# Tonuino_V1_0.net
KiCad netlist of a schematic drawn in EAGLE
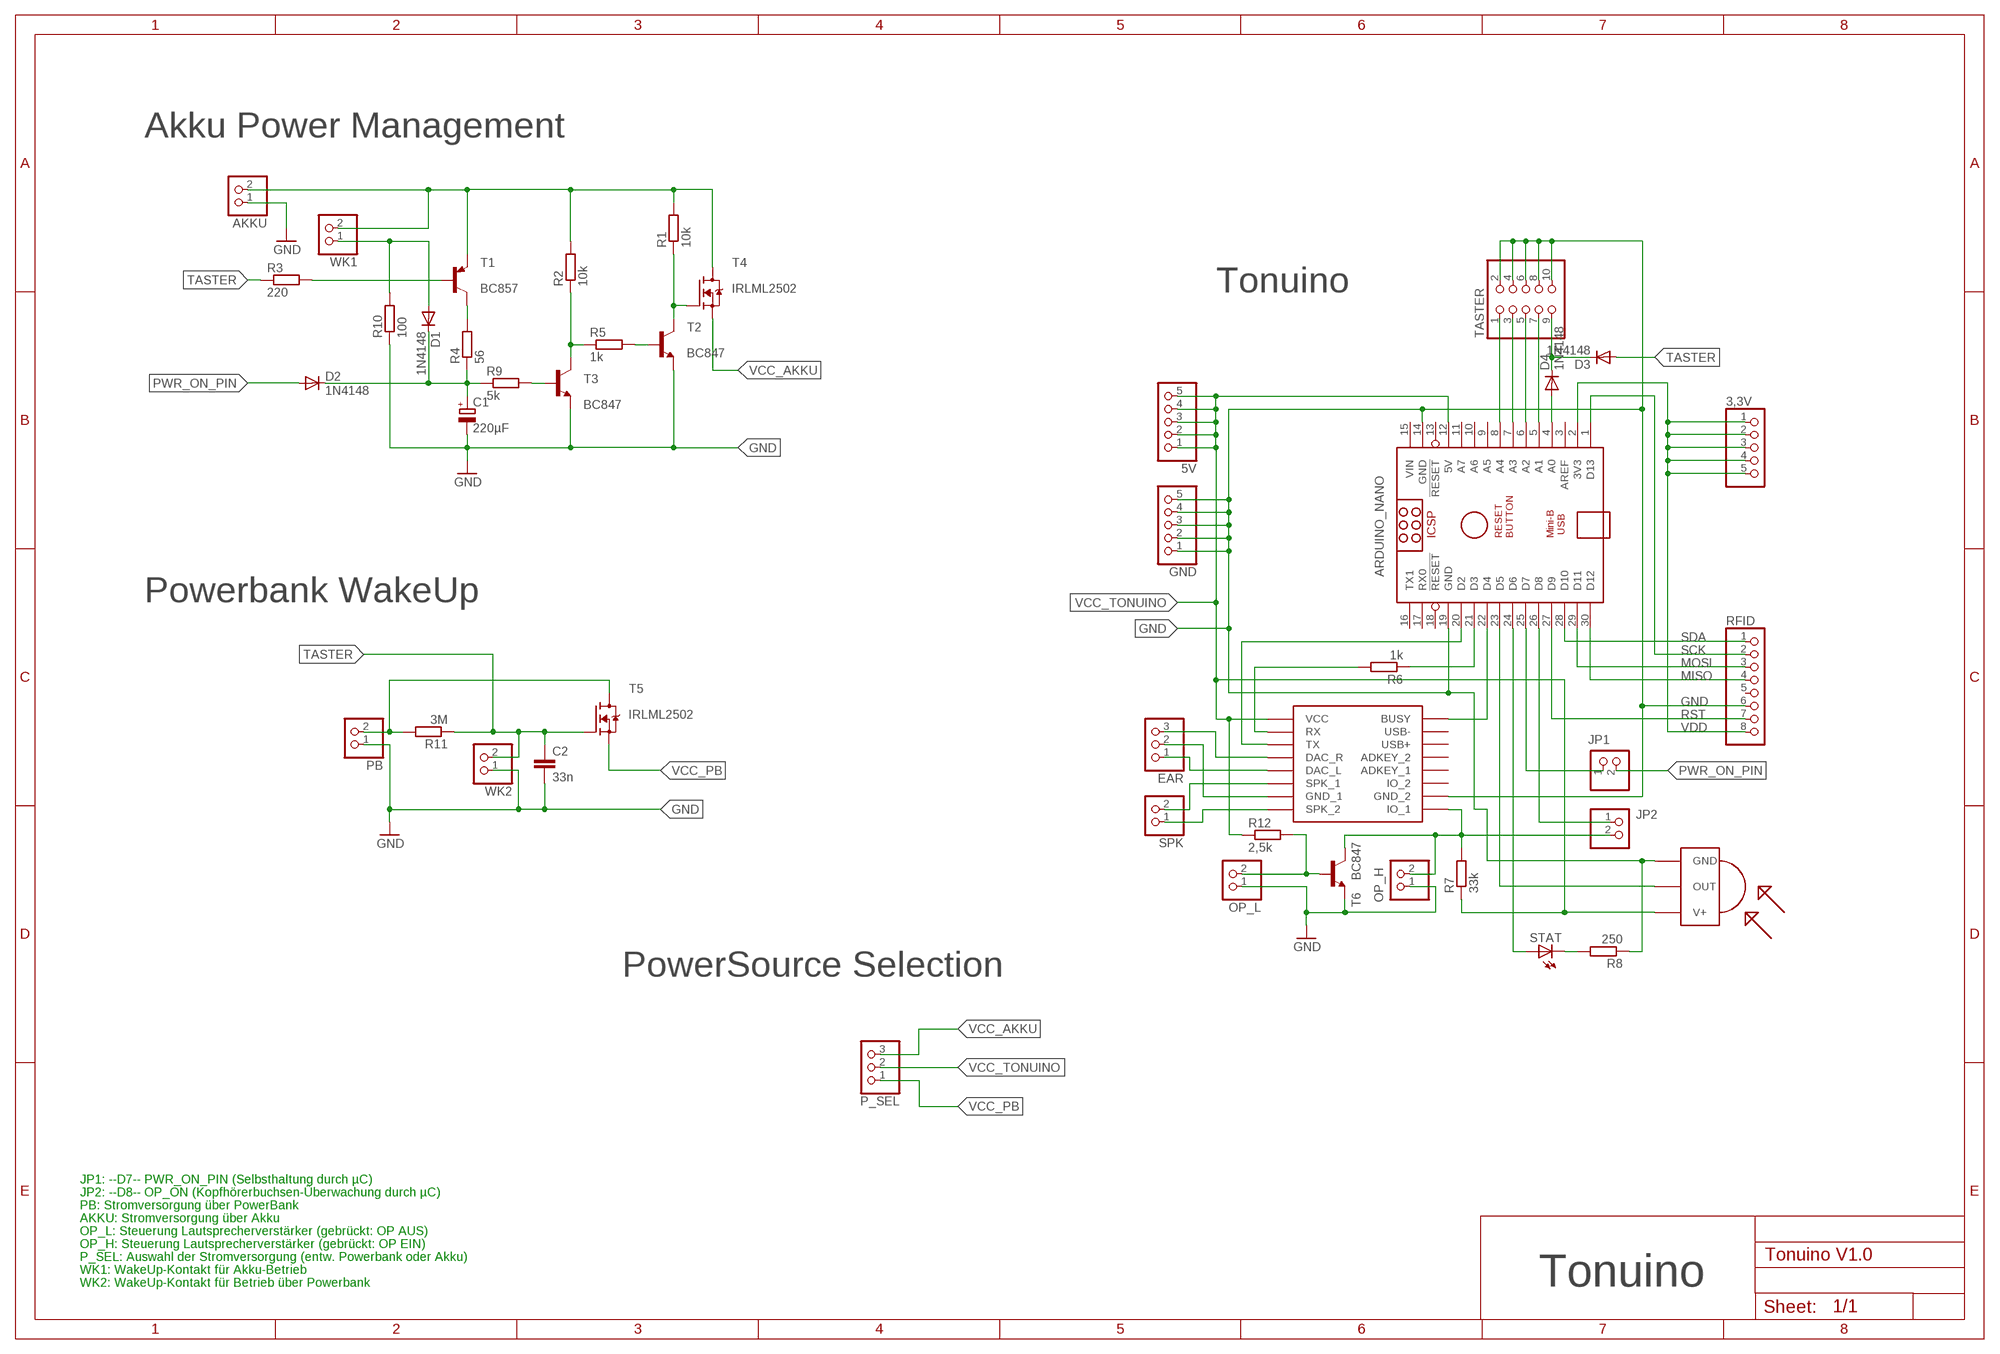
[diagram p0: schematic, sheet 1]

(export (version "E")
  (design (tool "Eeschema 10.0.6"))
  (components
    (comp (ref "3,3V")
      (value "PINHD-1X5")
      (footprint "eagle-import:1X05")
      (libsource (lib "eagle-import") (part "PINHD-1X5"))
    )
    (comp (ref "5V")
      (value "PINHD-1X5")
      (footprint "eagle-import:1X05")
      (libsource (lib "eagle-import") (part "PINHD-1X5"))
    )
    (comp (ref "AKKU")
      (value "PINHD-1X2")
      (footprint "eagle-import:1X02")
      (libsource (lib "eagle-import") (part "PINHD-1X2"))
    )
    (comp (ref "ARDUINO_NANO")
      (value "ARDUINO_NANO")
      (footprint "eagle-import:ARDUINO_NANO")
      (libsource (lib "eagle-import") (part "ARDUINO_NANO"))
    )
    (comp (ref "C1")
      (value "220µF")
      (footprint "eagle-import:E5-13")
      (libsource (lib "eagle-import") (part "CPOL-EUE5-13"))
    )
    (comp (ref "C2")
      (value "33n")
      (footprint "eagle-import:C0805")
      (libsource (lib "eagle-import") (part "C-EUC0805"))
    )
    (comp (ref "D1")
      (value "1N4148")
      (footprint "eagle-import:SOD323-W")
      (libsource (lib "eagle-import") (part "DIODE-SOD323-W"))
    )
    (comp (ref "D2")
      (value "1N4148")
      (footprint "eagle-import:SOD323-W")
      (libsource (lib "eagle-import") (part "DIODE-SOD323-W"))
    )
    (comp (ref "D3")
      (value "1N4148")
      (footprint "eagle-import:SOD323-W")
      (libsource (lib "eagle-import") (part "DIODE-SOD323-W"))
    )
    (comp (ref "D4")
      (value "1N4148")
      (footprint "eagle-import:SOD323-W")
      (libsource (lib "eagle-import") (part "DIODE-SOD323-W"))
    )
    (comp (ref "EAR")
      (value "PINHD-1X3")
      (footprint "eagle-import:1X03")
      (libsource (lib "eagle-import") (part "PINHD-1X3"))
    )
    (comp (ref "GND")
      (value "PINHD-1X5")
      (footprint "eagle-import:1X05")
      (libsource (lib "eagle-import") (part "PINHD-1X5"))
    )
    (comp (ref "JP1")
      (value "PINHD-1X2")
      (footprint "eagle-import:1X02")
      (libsource (lib "eagle-import") (part "PINHD-1X2"))
    )
    (comp (ref "JP2")
      (value "PINHD-1X2")
      (footprint "eagle-import:1X02")
      (libsource (lib "eagle-import") (part "PINHD-1X2"))
    )
    (comp (ref "OP_H")
      (value "PINHD-1X2")
      (footprint "eagle-import:1X02")
      (libsource (lib "eagle-import") (part "PINHD-1X2"))
    )
    (comp (ref "OP_L")
      (value "PINHD-1X2")
      (footprint "eagle-import:1X02")
      (libsource (lib "eagle-import") (part "PINHD-1X2"))
    )
    (comp (ref "PB")
      (value "PINHD-1X2")
      (footprint "eagle-import:1X02")
      (libsource (lib "eagle-import") (part "PINHD-1X2"))
    )
    (comp (ref "P_SEL")
      (value "PINHD-1X3")
      (footprint "eagle-import:1X03")
      (libsource (lib "eagle-import") (part "PINHD-1X3"))
    )
    (comp (ref "R1")
      (value "10k")
      (footprint "eagle-import:R1206")
      (libsource (lib "eagle-import") (part "R-EU_R1206"))
    )
    (comp (ref "R2")
      (value "10k")
      (footprint "eagle-import:R1206")
      (libsource (lib "eagle-import") (part "R-EU_R1206"))
    )
    (comp (ref "R3")
      (value "220")
      (footprint "eagle-import:R1206")
      (libsource (lib "eagle-import") (part "R-EU_R1206"))
    )
    (comp (ref "R4")
      (value "56")
      (footprint "eagle-import:R1206")
      (libsource (lib "eagle-import") (part "R-EU_R1206"))
    )
    (comp (ref "R5")
      (value "1k")
      (footprint "eagle-import:R1206")
      (libsource (lib "eagle-import") (part "R-EU_R1206"))
    )
    (comp (ref "R6")
      (value "1k")
      (footprint "eagle-import:R1206")
      (libsource (lib "eagle-import") (part "R-EU_R1206"))
    )
    (comp (ref "R7")
      (value "33k")
      (footprint "eagle-import:R1206")
      (libsource (lib "eagle-import") (part "R-EU_R1206"))
    )
    (comp (ref "R8")
      (value "250")
      (footprint "eagle-import:R1206")
      (libsource (lib "eagle-import") (part "R-EU_R1206"))
    )
    (comp (ref "R9")
      (value "5k")
      (footprint "eagle-import:R1206")
      (libsource (lib "eagle-import") (part "R-EU_R1206"))
    )
    (comp (ref "R10")
      (value "100")
      (footprint "eagle-import:R1206")
      (libsource (lib "eagle-import") (part "R-EU_R1206"))
    )
    (comp (ref "R11")
      (value "3M")
      (footprint "eagle-import:R1206")
      (libsource (lib "eagle-import") (part "R-EU_R1206"))
    )
    (comp (ref "R12")
      (value "2,5k")
      (footprint "eagle-import:R1206")
      (libsource (lib "eagle-import") (part "R-EU_R1206"))
    )
    (comp (ref "RFID")
      (value "PINHD-1X8")
      (footprint "eagle-import:1X08")
      (libsource (lib "eagle-import") (part "PINHD-1X8"))
    )
    (comp (ref "SPK")
      (value "PINHD-1X2")
      (footprint "eagle-import:1X02")
      (libsource (lib "eagle-import") (part "PINHD-1X2"))
    )
    (comp (ref "STAT")
      (value "LED5MM")
      (footprint "eagle-import:LED5MM")
      (libsource (lib "eagle-import") (part "LED5MM"))
    )
    (comp (ref "T1")
      (value "BC857")
      (footprint "eagle-import:SOT23-BEC")
      (libsource (lib "eagle-import") (part "-PNP-SOT23-BECBC857A"))
    )
    (comp (ref "T2")
      (value "BC847")
      (footprint "eagle-import:SOT23")
      (libsource (lib "eagle-import") (part "BC847"))
    )
    (comp (ref "T3")
      (value "BC847")
      (footprint "eagle-import:SOT23")
      (libsource (lib "eagle-import") (part "BC847"))
    )
    (comp (ref "T4")
      (value "IRLML2502")
      (footprint "eagle-import:SOT23")
      (libsource (lib "eagle-import") (part "IRLML2502"))
    )
    (comp (ref "T5")
      (value "IRLML2502")
      (footprint "eagle-import:SOT23")
      (libsource (lib "eagle-import") (part "IRLML2502"))
    )
    (comp (ref "T6")
      (value "BC847")
      (footprint "eagle-import:SOT23")
      (libsource (lib "eagle-import") (part "BC847"))
    )
    (comp (ref "TASTER")
      (value "PINHD-2X5")
      (footprint "eagle-import:2X05")
      (libsource (lib "eagle-import") (part "PINHD-2X5"))
    )
    (comp (ref "TSOP1")
      (value "TSOP1730")
      (footprint "eagle-import:TSOP17XX")
      (libsource (lib "eagle-import") (part "TSOP1730"))
    )
    (comp (ref "U$2")
      (value "DFPLAYER")
      (footprint "eagle-import:DFPLAYER")
      (libsource (lib "eagle-import") (part "DFPLAYER"))
    )
    (comp (ref "WK1")
      (value "PINHD-1X2")
      (footprint "eagle-import:1X02")
      (libsource (lib "eagle-import") (part "PINHD-1X2"))
    )
    (comp (ref "WK2")
      (value "PINHD-1X2")
      (footprint "eagle-import:1X02")
      (libsource (lib "eagle-import") (part "PINHD-1X2"))
    )
  )
  (nets
    (net (code "1") (name "/MISO") (class "Default")
      (node (ref "ARDUINO_NANO") (pin "30") (pinfunction "D12_30") (pintype "bidirectional"))
      (node (ref "RFID") (pin "4") (pinfunction "4_4") (pintype "passive"))
    )
    (net (code "2") (name "/MOSI") (class "Default")
      (node (ref "ARDUINO_NANO") (pin "29") (pinfunction "D11_29") (pintype "bidirectional"))
      (node (ref "RFID") (pin "3") (pinfunction "3_3") (pintype "passive"))
    )
    (net (code "3") (name "/RST") (class "Default")
      (node (ref "ARDUINO_NANO") (pin "27") (pinfunction "D9_27") (pintype "bidirectional"))
      (node (ref "RFID") (pin "7") (pinfunction "7_7") (pintype "passive"))
    )
    (net (code "4") (name "/SCK") (class "Default")
      (node (ref "ARDUINO_NANO") (pin "1") (pinfunction "D13_1") (pintype "bidirectional"))
      (node (ref "RFID") (pin "2") (pinfunction "2_2") (pintype "passive"))
    )
    (net (code "5") (name "/SDA") (class "Default")
      (node (ref "ARDUINO_NANO") (pin "28") (pinfunction "D10_28") (pintype "bidirectional"))
      (node (ref "RFID") (pin "1") (pinfunction "1_1") (pintype "passive"))
    )
    (net (code "6") (name "/VDD") (class "Default")
      (node (ref "3,3V") (pin "1") (pinfunction "1_1") (pintype "passive"))
      (node (ref "3,3V") (pin "2") (pinfunction "2_2") (pintype "passive"))
      (node (ref "3,3V") (pin "3") (pinfunction "3_3") (pintype "passive"))
      (node (ref "3,3V") (pin "4") (pinfunction "4_4") (pintype "passive"))
      (node (ref "3,3V") (pin "5") (pinfunction "5_5") (pintype "passive"))
      (node (ref "ARDUINO_NANO") (pin "2") (pinfunction "3V3_2") (pintype "output"))
      (node (ref "RFID") (pin "8") (pinfunction "8_8") (pintype "passive"))
    )
    (net (code "7") (name "/VIN") (class "Default")
      (node (ref "ARDUINO_NANO") (pin "15") (pinfunction "VIN_15") (pintype "power_in"))
    )
    (net (code "8") (name "GND") (class "Default")
      (node (ref "AKKU") (pin "1") (pinfunction "1_1") (pintype "passive"))
      (node (ref "ARDUINO_NANO") (pin "14") (pinfunction "GND_14") (pintype "power_in"))
      (node (ref "ARDUINO_NANO") (pin "19") (pinfunction "GND_19") (pintype "power_in"))
      (node (ref "C1") (pin "-") (pinfunction "-_-") (pintype "passive"))
      (node (ref "C2") (pin "2") (pinfunction "2_2") (pintype "passive"))
      (node (ref "GND") (pin "1") (pinfunction "1_1") (pintype "passive"))
      (node (ref "GND") (pin "2") (pinfunction "2_2") (pintype "passive"))
      (node (ref "GND") (pin "3") (pinfunction "3_3") (pintype "passive"))
      (node (ref "GND") (pin "4") (pinfunction "4_4") (pintype "passive"))
      (node (ref "GND") (pin "5") (pinfunction "5_5") (pintype "passive"))
      (node (ref "OP_H") (pin "1") (pinfunction "1_1") (pintype "passive"))
      (node (ref "OP_L") (pin "1") (pinfunction "1_1") (pintype "passive"))
      (node (ref "PB") (pin "1") (pinfunction "1_1") (pintype "passive"))
      (node (ref "R10") (pin "1") (pinfunction "1_1") (pintype "passive"))
      (node (ref "R8") (pin "1") (pinfunction "1_1") (pintype "passive"))
      (node (ref "RFID") (pin "6") (pinfunction "6_6") (pintype "passive"))
      (node (ref "T2") (pin "2") (pinfunction "E_2") (pintype "passive"))
      (node (ref "T3") (pin "2") (pinfunction "E_2") (pintype "passive"))
      (node (ref "T6") (pin "2") (pinfunction "E_2") (pintype "passive"))
      (node (ref "TASTER") (pin "10") (pinfunction "10_10") (pintype "passive"))
      (node (ref "TASTER") (pin "2") (pinfunction "2_2") (pintype "passive"))
      (node (ref "TASTER") (pin "4") (pinfunction "4_4") (pintype "passive"))
      (node (ref "TASTER") (pin "6") (pinfunction "6_6") (pintype "passive"))
      (node (ref "TASTER") (pin "8") (pinfunction "8_8") (pintype "passive"))
      (node (ref "TSOP1") (pin "GND") (pinfunction "GND_GND") (pintype "bidirectional"))
      (node (ref "U$2") (pin "GND_2") (pinfunction "GND_2_GND_2") (pintype "bidirectional"))
      (node (ref "WK2") (pin "1") (pinfunction "1_1") (pintype "passive"))
    )
    (net (code "9") (name "Net-(ARDUINO_NANO-A0)") (class "Default")
      (node (ref "ARDUINO_NANO") (pin "4") (pinfunction "A0_4") (pintype "bidirectional"))
      (node (ref "D4") (pin "A") (pinfunction "A_A") (pintype "passive"))
    )
    (net (code "10") (name "Net-(ARDUINO_NANO-A1)") (class "Default")
      (node (ref "ARDUINO_NANO") (pin "5") (pinfunction "A1_5") (pintype "bidirectional"))
      (node (ref "TASTER") (pin "7") (pinfunction "7_7") (pintype "passive"))
    )
    (net (code "11") (name "Net-(ARDUINO_NANO-A2)") (class "Default")
      (node (ref "ARDUINO_NANO") (pin "6") (pinfunction "A2_6") (pintype "bidirectional"))
      (node (ref "TASTER") (pin "5") (pinfunction "5_5") (pintype "passive"))
    )
    (net (code "12") (name "Net-(ARDUINO_NANO-A3)") (class "Default")
      (node (ref "ARDUINO_NANO") (pin "7") (pinfunction "A3_7") (pintype "bidirectional"))
      (node (ref "TASTER") (pin "3") (pinfunction "3_3") (pintype "passive"))
    )
    (net (code "13") (name "Net-(ARDUINO_NANO-A4)") (class "Default")
      (node (ref "ARDUINO_NANO") (pin "8") (pinfunction "A4_8") (pintype "bidirectional"))
      (node (ref "TASTER") (pin "1") (pinfunction "1_1") (pintype "passive"))
    )
    (net (code "14") (name "Net-(ARDUINO_NANO-D2)") (class "Default")
      (node (ref "ARDUINO_NANO") (pin "20") (pinfunction "D2_20") (pintype "bidirectional"))
      (node (ref "U$2") (pin "TX") (pinfunction "TX_TX") (pintype "bidirectional"))
    )
    (net (code "15") (name "Net-(ARDUINO_NANO-D3)") (class "Default")
      (node (ref "ARDUINO_NANO") (pin "21") (pinfunction "D3_21") (pintype "bidirectional"))
      (node (ref "R6") (pin "1") (pinfunction "1_1") (pintype "passive"))
    )
    (net (code "16") (name "Net-(ARDUINO_NANO-D4)") (class "Default")
      (node (ref "ARDUINO_NANO") (pin "22") (pinfunction "D4_22") (pintype "bidirectional"))
      (node (ref "U$2") (pin "BUSY") (pinfunction "BUSY_BUSY") (pintype "bidirectional"))
    )
    (net (code "17") (name "Net-(ARDUINO_NANO-D5)") (class "Default")
      (node (ref "ARDUINO_NANO") (pin "23") (pinfunction "D5_23") (pintype "bidirectional"))
      (node (ref "TSOP1") (pin "OUT") (pinfunction "OUT_OUT") (pintype "bidirectional"))
    )
    (net (code "18") (name "Net-(ARDUINO_NANO-D6)") (class "Default")
      (node (ref "ARDUINO_NANO") (pin "24") (pinfunction "D6_24") (pintype "bidirectional"))
      (node (ref "STAT") (pin "A") (pinfunction "A_A") (pintype "passive"))
    )
    (net (code "19") (name "Net-(ARDUINO_NANO-D7)") (class "Default")
      (node (ref "ARDUINO_NANO") (pin "25") (pinfunction "D7_25") (pintype "bidirectional"))
      (node (ref "JP1") (pin "1") (pinfunction "1_1") (pintype "passive"))
    )
    (net (code "20") (name "Net-(ARDUINO_NANO-D8)") (class "Default")
      (node (ref "ARDUINO_NANO") (pin "26") (pinfunction "D8_26") (pintype "bidirectional"))
      (node (ref "JP2") (pin "1") (pinfunction "1_1") (pintype "passive"))
    )
    (net (code "21") (name "Net-(C1-Pad+)") (class "Default")
      (node (ref "C1") (pin "+") (pinfunction "+_+") (pintype "passive"))
      (node (ref "D1") (pin "C") (pinfunction "C_C") (pintype "passive"))
      (node (ref "D2") (pin "C") (pinfunction "C_C") (pintype "passive"))
      (node (ref "R4") (pin "1") (pinfunction "1_1") (pintype "passive"))
      (node (ref "R9") (pin "1") (pinfunction "1_1") (pintype "passive"))
    )
    (net (code "22") (name "Net-(D1-PadA)") (class "Default")
      (node (ref "D1") (pin "A") (pinfunction "A_A") (pintype "passive"))
      (node (ref "R10") (pin "2") (pinfunction "2_2") (pintype "passive"))
      (node (ref "WK1") (pin "1") (pinfunction "1_1") (pintype "passive"))
    )
    (net (code "23") (name "Net-(D3-PadC)") (class "Default")
      (node (ref "D3") (pin "C") (pinfunction "C_C") (pintype "passive"))
      (node (ref "D4") (pin "C") (pinfunction "C_C") (pintype "passive"))
      (node (ref "TASTER") (pin "9") (pinfunction "9_9") (pintype "passive"))
    )
    (net (code "24") (name "Net-(EAR-Pad1)") (class "Default")
      (node (ref "EAR") (pin "1") (pinfunction "1_1") (pintype "passive"))
      (node (ref "U$2") (pin "DAC_L") (pinfunction "DAC_L_DAC_L") (pintype "bidirectional"))
    )
    (net (code "25") (name "Net-(EAR-Pad2)") (class "Default")
      (node (ref "EAR") (pin "2") (pinfunction "2_2") (pintype "passive"))
      (node (ref "U$2") (pin "GND_1") (pinfunction "GND_1_GND_1") (pintype "bidirectional"))
    )
    (net (code "26") (name "Net-(EAR-Pad3)") (class "Default")
      (node (ref "EAR") (pin "3") (pinfunction "3_3") (pintype "passive"))
      (node (ref "U$2") (pin "DAC_R") (pinfunction "DAC_R_DAC_R") (pintype "bidirectional"))
    )
    (net (code "27") (name "Net-(R3-Pad2)") (class "Default")
      (node (ref "R3") (pin "2") (pinfunction "2_2") (pintype "passive"))
      (node (ref "T1") (pin "B") (pinfunction "B_B") (pintype "passive"))
    )
    (net (code "28") (name "Net-(R4-Pad2)") (class "Default")
      (node (ref "R4") (pin "2") (pinfunction "2_2") (pintype "passive"))
      (node (ref "T1") (pin "C") (pinfunction "C_C") (pintype "passive"))
    )
    (net (code "29") (name "Net-(R6-Pad2)") (class "Default")
      (node (ref "R6") (pin "2") (pinfunction "2_2") (pintype "passive"))
      (node (ref "U$2") (pin "RX") (pinfunction "RX_RX") (pintype "bidirectional"))
    )
    (net (code "30") (name "Net-(STAT-C)") (class "Default")
      (node (ref "R8") (pin "2") (pinfunction "2_2") (pintype "passive"))
      (node (ref "STAT") (pin "K") (pinfunction "C_K") (pintype "passive"))
    )
    (net (code "31") (name "Net-(T2-B)") (class "Default")
      (node (ref "R5") (pin "2") (pinfunction "2_2") (pintype "passive"))
      (node (ref "T2") (pin "1") (pinfunction "B_1") (pintype "passive"))
    )
    (net (code "32") (name "Net-(T2-C)") (class "Default")
      (node (ref "R1") (pin "1") (pinfunction "1_1") (pintype "passive"))
      (node (ref "T2") (pin "3") (pinfunction "C_3") (pintype "passive"))
      (node (ref "T4") (pin "1") (pinfunction "G_1") (pintype "passive"))
    )
    (net (code "33") (name "Net-(T3-B)") (class "Default")
      (node (ref "R9") (pin "2") (pinfunction "2_2") (pintype "passive"))
      (node (ref "T3") (pin "1") (pinfunction "B_1") (pintype "passive"))
    )
    (net (code "34") (name "Net-(T3-C)") (class "Default")
      (node (ref "R2") (pin "1") (pinfunction "1_1") (pintype "passive"))
      (node (ref "R5") (pin "1") (pinfunction "1_1") (pintype "passive"))
      (node (ref "T3") (pin "3") (pinfunction "C_3") (pintype "passive"))
    )
    (net (code "35") (name "Net-(T4-D)") (class "Default")
      (node (ref "AKKU") (pin "2") (pinfunction "2_2") (pintype "passive"))
      (node (ref "R1") (pin "2") (pinfunction "2_2") (pintype "passive"))
      (node (ref "R2") (pin "2") (pinfunction "2_2") (pintype "passive"))
      (node (ref "T1") (pin "E") (pinfunction "E_E") (pintype "passive"))
      (node (ref "T4") (pin "3") (pinfunction "D_3") (pintype "passive"))
      (node (ref "WK1") (pin "2") (pinfunction "2_2") (pintype "passive"))
    )
    (net (code "36") (name "Net-(T5-D)") (class "Default")
      (node (ref "PB") (pin "2") (pinfunction "2_2") (pintype "passive"))
      (node (ref "R11") (pin "2") (pinfunction "2_2") (pintype "passive"))
      (node (ref "T5") (pin "3") (pinfunction "D_3") (pintype "passive"))
    )
    (net (code "37") (name "Net-(T6-B)") (class "Default")
      (node (ref "OP_L") (pin "2") (pinfunction "2_2") (pintype "passive"))
      (node (ref "R12") (pin "2") (pinfunction "2_2") (pintype "passive"))
      (node (ref "T6") (pin "1") (pinfunction "B_1") (pintype "passive"))
    )
    (net (code "38") (name "Net-(T6-C)") (class "Default")
      (node (ref "JP2") (pin "2") (pinfunction "2_2") (pintype "passive"))
      (node (ref "OP_H") (pin "2") (pinfunction "2_2") (pintype "passive"))
      (node (ref "R7") (pin "2") (pinfunction "2_2") (pintype "passive"))
      (node (ref "T6") (pin "3") (pinfunction "C_3") (pintype "passive"))
      (node (ref "U$2") (pin "IO1") (pinfunction "IO_1_IO1") (pintype "bidirectional"))
    )
    (net (code "39") (name "Net-(U$2-SPK_1)") (class "Default")
      (node (ref "SPK") (pin "2") (pinfunction "2_2") (pintype "passive"))
      (node (ref "U$2") (pin "SPK1") (pinfunction "SPK_1_SPK1") (pintype "bidirectional"))
    )
    (net (code "40") (name "Net-(U$2-SPK_2)") (class "Default")
      (node (ref "SPK") (pin "1") (pinfunction "1_1") (pintype "passive"))
      (node (ref "U$2") (pin "SPK2") (pinfunction "SPK_2_SPK2") (pintype "bidirectional"))
    )
    (net (code "41") (name "PWR_ON_PIN") (class "Default")
      (node (ref "D2") (pin "A") (pinfunction "A_A") (pintype "passive"))
      (node (ref "JP1") (pin "2") (pinfunction "2_2") (pintype "passive"))
    )
    (net (code "42") (name "TASTER") (class "Default")
      (node (ref "C2") (pin "1") (pinfunction "1_1") (pintype "passive"))
      (node (ref "D3") (pin "A") (pinfunction "A_A") (pintype "passive"))
      (node (ref "R11") (pin "1") (pinfunction "1_1") (pintype "passive"))
      (node (ref "R3") (pin "1") (pinfunction "1_1") (pintype "passive"))
      (node (ref "T5") (pin "1") (pinfunction "G_1") (pintype "passive"))
      (node (ref "WK2") (pin "2") (pinfunction "2_2") (pintype "passive"))
    )
    (net (code "43") (name "VCC_AKKU") (class "Default")
      (node (ref "P_SEL") (pin "3") (pinfunction "3_3") (pintype "passive"))
      (node (ref "T4") (pin "2") (pinfunction "S_2") (pintype "passive"))
    )
    (net (code "44") (name "VCC_PB") (class "Default")
      (node (ref "P_SEL") (pin "1") (pinfunction "1_1") (pintype "passive"))
      (node (ref "T5") (pin "2") (pinfunction "S_2") (pintype "passive"))
    )
    (net (code "45") (name "VCC_TONUINO") (class "Default")
      (node (ref "5V") (pin "1") (pinfunction "1_1") (pintype "passive"))
      (node (ref "5V") (pin "2") (pinfunction "2_2") (pintype "passive"))
      (node (ref "5V") (pin "3") (pinfunction "3_3") (pintype "passive"))
      (node (ref "5V") (pin "4") (pinfunction "4_4") (pintype "passive"))
      (node (ref "5V") (pin "5") (pinfunction "5_5") (pintype "passive"))
      (node (ref "ARDUINO_NANO") (pin "12") (pinfunction "5V_12") (pintype "power_in"))
      (node (ref "P_SEL") (pin "2") (pinfunction "2_2") (pintype "passive"))
      (node (ref "R12") (pin "1") (pinfunction "1_1") (pintype "passive"))
      (node (ref "R7") (pin "1") (pinfunction "1_1") (pintype "passive"))
      (node (ref "TSOP1") (pin "V+") (pinfunction "V+_V+") (pintype "bidirectional"))
      (node (ref "U$2") (pin "VCC") (pinfunction "VCC_VCC") (pintype "bidirectional"))
    )
    (net (code "46") (name "unconnected-(ARDUINO_NANO-A5-Pad9)") (class "Default")
      (node (ref "ARDUINO_NANO") (pin "9") (pinfunction "A5_9") (pintype "bidirectional"))
    )
    (net (code "47") (name "unconnected-(ARDUINO_NANO-A6-Pad10)") (class "Default")
      (node (ref "ARDUINO_NANO") (pin "10") (pinfunction "A6_10") (pintype "bidirectional"))
    )
    (net (code "48") (name "unconnected-(ARDUINO_NANO-A7-Pad11)") (class "Default")
      (node (ref "ARDUINO_NANO") (pin "11") (pinfunction "A7_11") (pintype "bidirectional"))
    )
    (net (code "49") (name "unconnected-(ARDUINO_NANO-AREF-Pad3)") (class "Default")
      (node (ref "ARDUINO_NANO") (pin "3") (pinfunction "AREF_3") (pintype "input"))
    )
    (net (code "50") (name "unconnected-(ARDUINO_NANO-RX0-Pad17)") (class "Default")
      (node (ref "ARDUINO_NANO") (pin "17") (pinfunction "RX0_17") (pintype "bidirectional"))
    )
    (net (code "51") (name "unconnected-(ARDUINO_NANO-TX1-Pad16)") (class "Default")
      (node (ref "ARDUINO_NANO") (pin "16") (pinfunction "TX1_16") (pintype "bidirectional"))
    )
    (net (code "52") (name "unconnected-(ARDUINO_NANO-~{RESET}-Pad13)") (class "Default")
      (node (ref "ARDUINO_NANO") (pin "13") (pinfunction "~{RESET}_13") (pintype "input"))
    )
    (net (code "53") (name "unconnected-(ARDUINO_NANO-~{RESET}-Pad18)") (class "Default")
      (node (ref "ARDUINO_NANO") (pin "18") (pinfunction "~{RESET}_18") (pintype "input"))
    )
    (net (code "54") (name "unconnected-(RFID-Pad5)") (class "Default")
      (node (ref "RFID") (pin "5") (pinfunction "5_5") (pintype "passive"))
    )
    (net (code "55") (name "unconnected-(U$2-ADKEY_1-PadADKEY1)") (class "Default")
      (node (ref "U$2") (pin "ADKEY1") (pinfunction "ADKEY_1_ADKEY1") (pintype "bidirectional"))
    )
    (net (code "56") (name "unconnected-(U$2-ADKEY_2-PadADKEY2)") (class "Default")
      (node (ref "U$2") (pin "ADKEY2") (pinfunction "ADKEY_2_ADKEY2") (pintype "bidirectional"))
    )
    (net (code "57") (name "unconnected-(U$2-IO_2-PadIO2)") (class "Default")
      (node (ref "U$2") (pin "IO2") (pinfunction "IO_2_IO2") (pintype "bidirectional"))
    )
    (net (code "58") (name "unconnected-(U$2-PadUSB+)") (class "Default")
      (node (ref "U$2") (pin "USB+") (pinfunction "USB+_USB+") (pintype "bidirectional"))
    )
    (net (code "59") (name "unconnected-(U$2-PadUSB-)") (class "Default")
      (node (ref "U$2") (pin "USB-") (pinfunction "USB-_USB-") (pintype "bidirectional"))
    )
  )
)
